# Adafruit_PiRTC_PCF8523.net
KiCad netlist of a schematic drawn in EAGLE
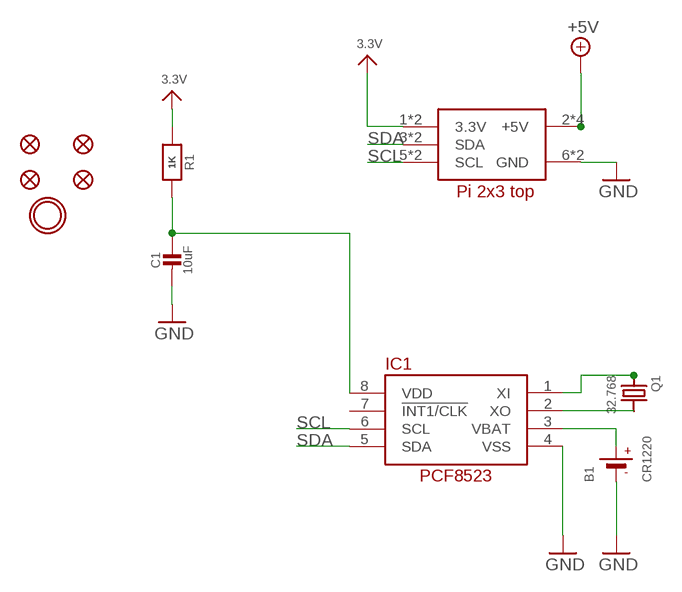
[diagram p0: schematic, sheet 1]

(export (version "E")
  (design (tool "Eeschema 10.0.6"))
  (components
    (comp (ref "B1")
      (value "CR1220")
      (footprint "eagle-import:CR1220")
      (libsource (lib "eagle-import") (part "BATTERYCR1220_SMT"))
    )
    (comp (ref "C1")
      (value "10uF")
      (footprint "eagle-import:0805-NO")
      (libsource (lib "eagle-import") (part "CAP_CERAMIC0805-NOOUTLINE"))
    )
    (comp (ref "FID1")
      (value "FIDUCIAL_1MM")
      (footprint "eagle-import:FIDUCIAL_1MM")
      (libsource (lib "eagle-import") (part "FIDUCIAL_1MM"))
    )
    (comp (ref "FID2")
      (value "FIDUCIAL_1MM")
      (footprint "eagle-import:FIDUCIAL_1MM")
      (libsource (lib "eagle-import") (part "FIDUCIAL_1MM"))
    )
    (comp (ref "FID3")
      (value "FIDUCIAL_1MM")
      (footprint "eagle-import:FIDUCIAL_1MM")
      (libsource (lib "eagle-import") (part "FIDUCIAL_1MM"))
    )
    (comp (ref "FID4")
      (value "FIDUCIAL_1MM")
      (footprint "eagle-import:FIDUCIAL_1MM")
      (libsource (lib "eagle-import") (part "FIDUCIAL_1MM"))
    )
    (comp (ref "IC1")
      (value "RTC_PCF8523T")
      (footprint "eagle-import:SOIC8_150MIL")
      (libsource (lib "eagle-import") (part "RTC_PCF8523T"))
    )
    (comp (ref "Q1")
      (value "32.768")
      (footprint "eagle-import:CRYSTAL_8X3.8")
      (libsource (lib "eagle-import") (part "CRYSTAL8.0X3.8"))
    )
    (comp (ref "R1")
      (value "1K")
      (footprint "eagle-import:0805-NO")
      (libsource (lib "eagle-import") (part "RESISTOR0805_NOOUTLINE"))
    )
    (comp (ref "RPI1")
      (value "RASPBERRYPI_2X3")
      (footprint "eagle-import:RASPBERRYPI_2X3_THMSMT")
      (libsource (lib "eagle-import") (part "RASPBERRYPI_2X3"))
    )
    (comp (ref "U$4")
      (value "MOUNTINGHOLE3.0THIN")
      (footprint "eagle-import:MOUNTINGHOLE_3.0_PLATEDTHIN")
      (libsource (lib "eagle-import") (part "MOUNTINGHOLE3.0THIN"))
    )
  )
  (nets
    (net (code "1") (name "+5V") (class "Default")
      (node (ref "RPI1") (pin "2") (pinfunction "+5V_2") (pintype "bidirectional"))
      (node (ref "RPI1") (pin "2'") (pinfunction "+5V_2'") (pintype "bidirectional"))
      (node (ref "RPI1") (pin "4") (pinfunction "+5V_4") (pintype "bidirectional"))
      (node (ref "RPI1") (pin "4'") (pinfunction "+5V_4'") (pintype "bidirectional"))
    )
    (net (code "2") (name "/SCL") (class "Default")
      (node (ref "IC1") (pin "6") (pinfunction "SCL_6") (pintype "bidirectional"))
      (node (ref "RPI1") (pin "5") (pinfunction "SCL_5") (pintype "bidirectional"))
      (node (ref "RPI1") (pin "5'") (pinfunction "SCL_5'") (pintype "bidirectional"))
    )
    (net (code "3") (name "/SDA") (class "Default")
      (node (ref "IC1") (pin "5") (pinfunction "SDA_5") (pintype "bidirectional"))
      (node (ref "RPI1") (pin "3") (pinfunction "SDA_3") (pintype "bidirectional"))
      (node (ref "RPI1") (pin "3'") (pinfunction "SDA_3'") (pintype "bidirectional"))
    )
    (net (code "4") (name "3.3V") (class "Default")
      (node (ref "R1") (pin "1") (pinfunction "1_1") (pintype "passive"))
      (node (ref "RPI1") (pin "1") (pinfunction "3.3V_1") (pintype "bidirectional"))
      (node (ref "RPI1") (pin "1'") (pinfunction "3.3V_1'") (pintype "bidirectional"))
    )
    (net (code "5") (name "GND") (class "Default")
      (node (ref "B1") (pin "-") (pinfunction "-_-") (pintype "passive"))
      (node (ref "C1") (pin "2") (pinfunction "2_2") (pintype "passive"))
      (node (ref "IC1") (pin "4") (pinfunction "VSS_4") (pintype "power_in"))
      (node (ref "RPI1") (pin "6") (pinfunction "GND_6") (pintype "bidirectional"))
      (node (ref "RPI1") (pin "6'") (pinfunction "GND_6'") (pintype "bidirectional"))
    )
    (net (code "6") (name "Net-(IC1-VBAT)") (class "Default")
      (node (ref "B1") (pin "+$1") (pinfunction "+_+$1") (pintype "passive"))
      (node (ref "B1") (pin "+$2") (pinfunction "+_+$2") (pintype "passive"))
      (node (ref "IC1") (pin "3") (pinfunction "VBAT_3") (pintype "power_in"))
    )
    (net (code "7") (name "Net-(IC1-VDD)") (class "Default")
      (node (ref "C1") (pin "1") (pinfunction "1_1") (pintype "passive"))
      (node (ref "IC1") (pin "8") (pinfunction "VDD_8") (pintype "power_in"))
      (node (ref "R1") (pin "2") (pinfunction "2_2") (pintype "passive"))
    )
    (net (code "8") (name "Net-(IC1-XI)") (class "Default")
      (node (ref "IC1") (pin "1") (pinfunction "XI_1") (pintype "input"))
      (node (ref "Q1") (pin "P$1") (pinfunction "1_P$1") (pintype "passive"))
    )
    (net (code "9") (name "Net-(IC1-XO)") (class "Default")
      (node (ref "IC1") (pin "2") (pinfunction "XO_2") (pintype "output"))
      (node (ref "Q1") (pin "P$4") (pinfunction "2_P$4") (pintype "passive"))
    )
    (net (code "10") (name "unconnected-(IC1-~{INT1{slash}CLK}-Pad7)") (class "Default")
      (node (ref "IC1") (pin "7") (pinfunction "~{INT1/CLK}_7") (pintype "output"))
    )
  )
)
